# TEMPLATE_Circuit.net
KiCad netlist of a schematic drawn in Altium Designer
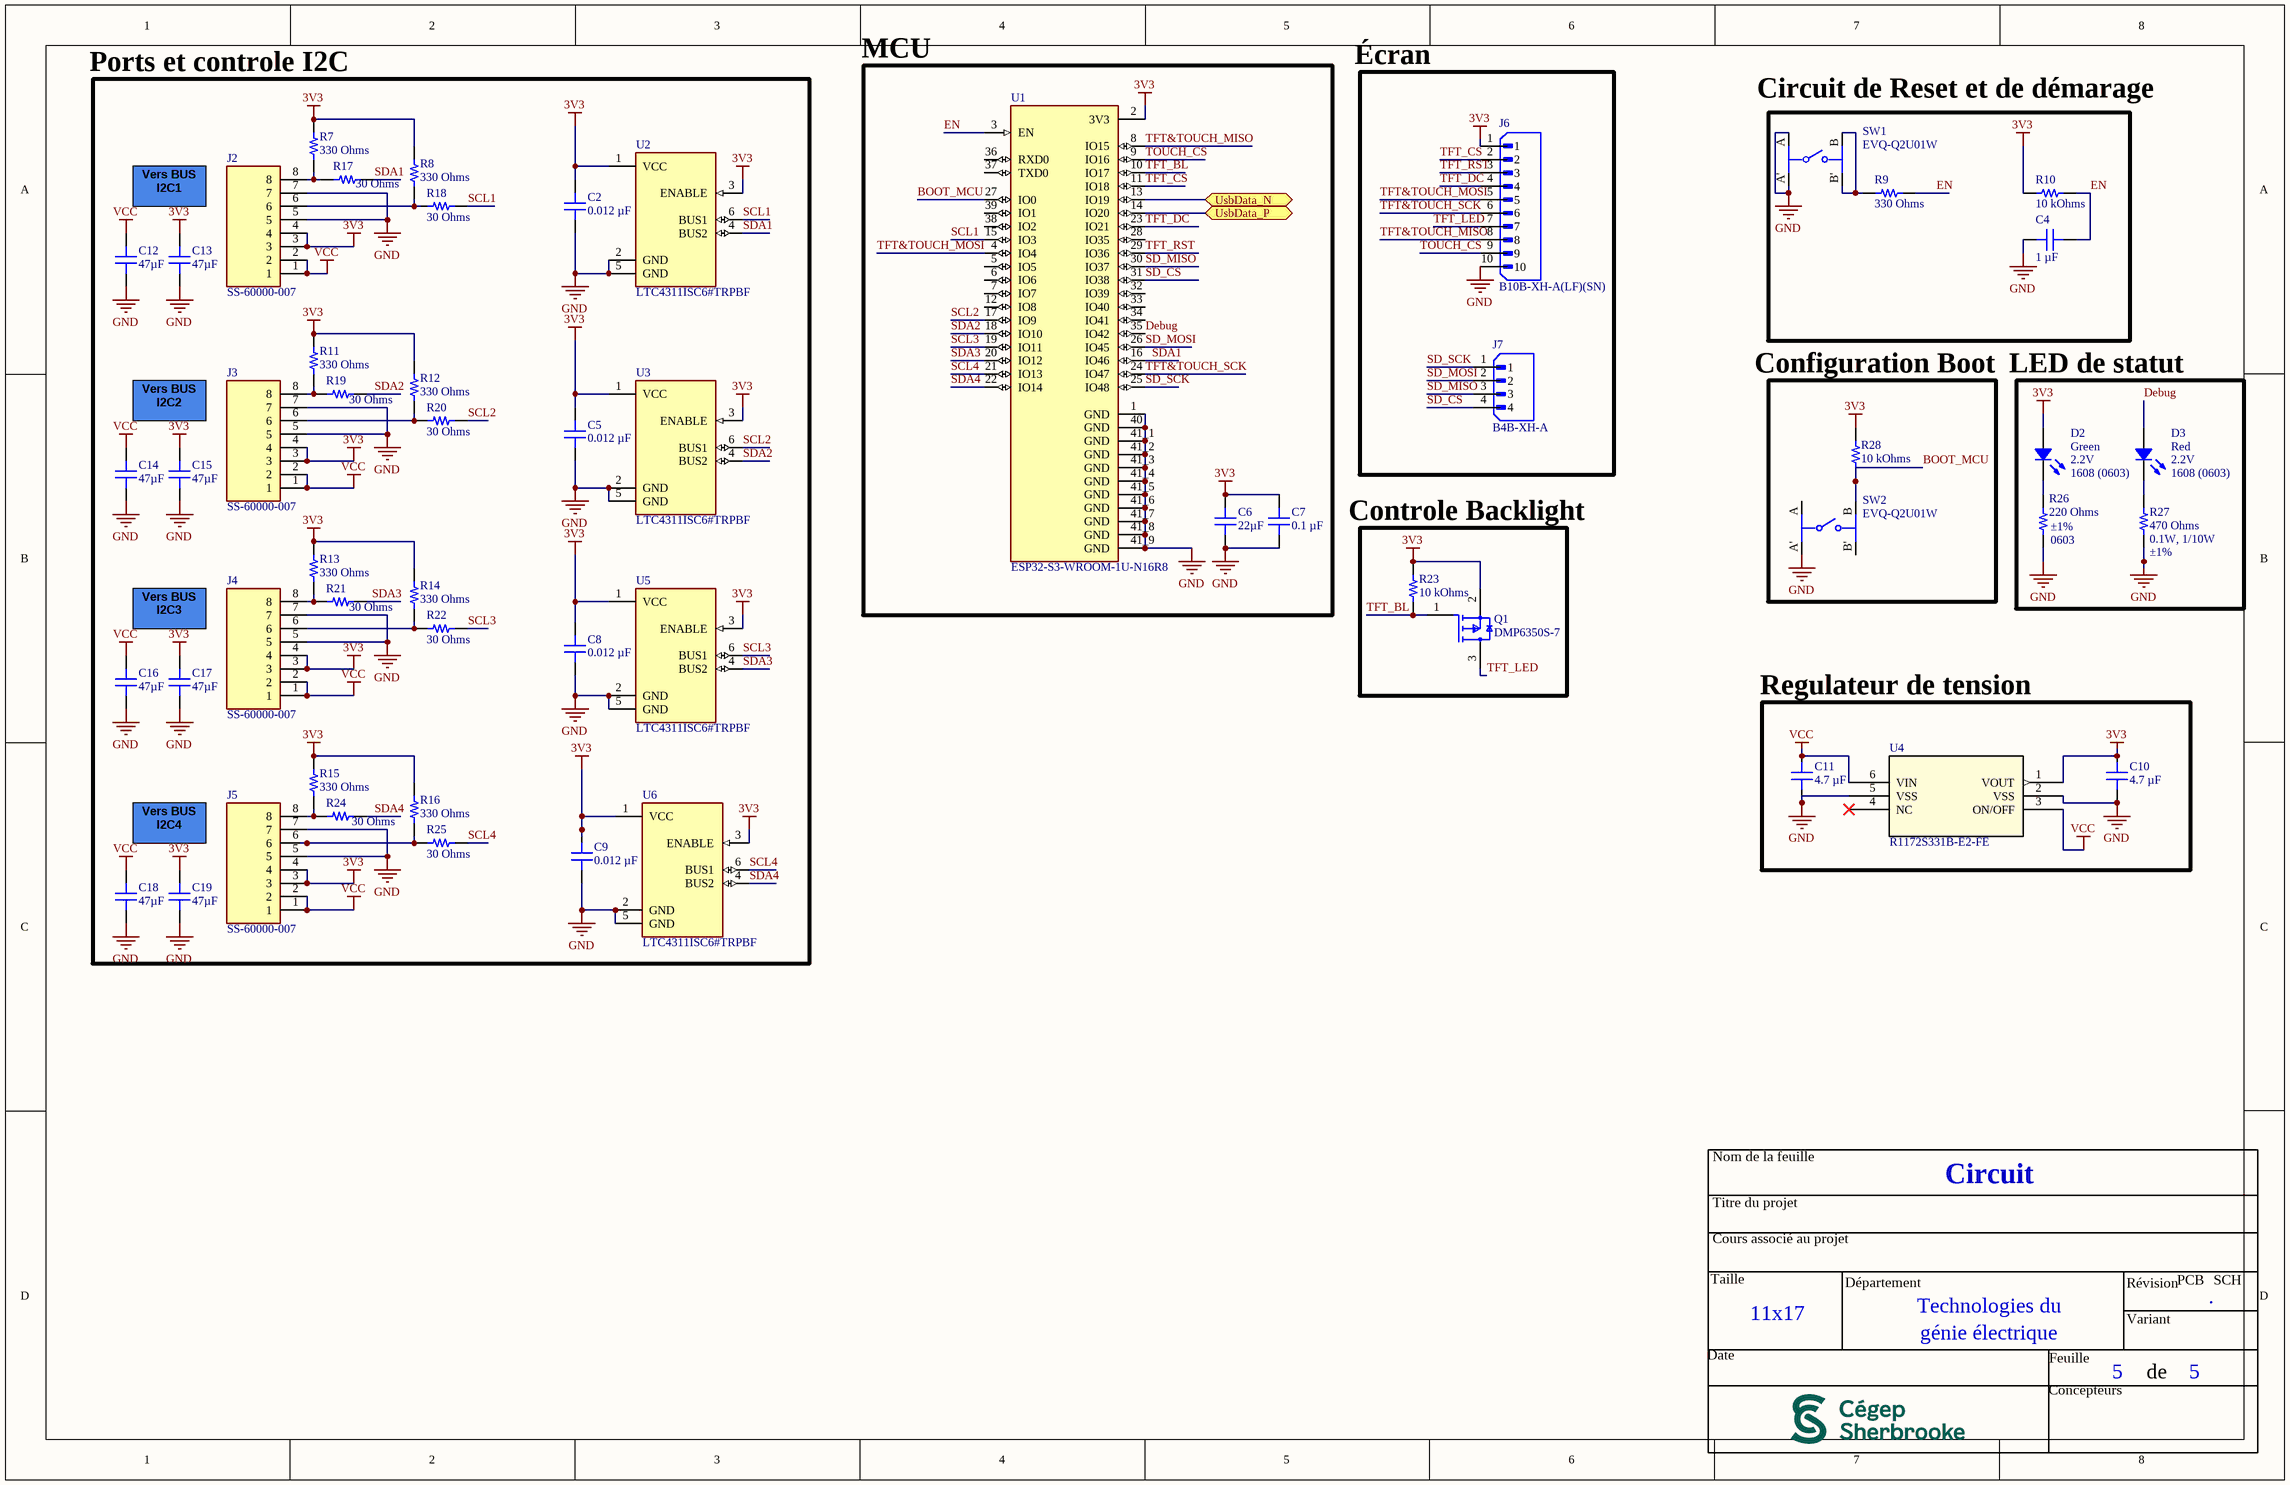
[diagram p0: TEMPLATE_Circuit.SchDoc]

(export (version "E")
  (design (tool "Eeschema 10.0.6"))
  (components
    (comp (ref "C2")
      (value "0.012 µF")
      (footprint "CAP 0603_1608")
      (description "CAP CER 0.012UF 16V X7R 0603")
      (fields (field (name "PART NUMBER") "CC0603KRX7R7BB123") (field (name "MANUFACTURER") "Yageo"))
      (libsource (lib "Celestial Altium Library - altium_library") (part "Capacitor"))
    )
    (comp (ref "C4")
      (value "1 µF")
      (footprint "CAP 0603_1608")
      (description "CAP CER 1UF 16V X7R 0603")
      (fields (field (name "PART NUMBER") "C0603X105M4RACAUTO") (field (name "MANUFACTURER") "KEMET"))
      (libsource (lib "Celestial Altium Library - altium_library") (part "Capacitor"))
    )
    (comp (ref "C5")
      (value "0.012 µF")
      (footprint "CAP 0603_1608")
      (description "CAP CER 0.012UF 16V X7R 0603")
      (fields (field (name "PART NUMBER") "CC0603KRX7R7BB123") (field (name "MANUFACTURER") "Yageo"))
      (libsource (lib "Celestial Altium Library - altium_library") (part "Capacitor"))
    )
    (comp (ref "C6")
      (value "22µF")
      (footprint "CAP 0603_1608")
      (description "CAP CER 22UF 6.3V X5R 0603")
      (fields (field (name "PART NUMBER") "06036D226MAT2A") (field (name "MANUFACTURER") "AVX Corporation"))
      (libsource (lib "Celestial Altium Library - altium_library") (part "Capacitor"))
    )
    (comp (ref "C7")
      (value "0.1 µF")
      (footprint "CAP 0603_1608")
      (description "CAP CER 0.1UF 16V X7R 0603")
      (fields (field (name "PART NUMBER") "C0603C104M4RAC7411") (field (name "MANUFACTURER") "KEMET"))
      (libsource (lib "Celestial Altium Library - altium_library") (part "Capacitor"))
    )
    (comp (ref "C8")
      (value "0.012 µF")
      (footprint "CAP 0603_1608")
      (description "CAP CER 0.012UF 16V X7R 0603")
      (fields (field (name "PART NUMBER") "CC0603KRX7R7BB123") (field (name "MANUFACTURER") "Yageo"))
      (libsource (lib "Celestial Altium Library - altium_library") (part "Capacitor"))
    )
    (comp (ref "C9")
      (value "0.012 µF")
      (footprint "CAP 0603_1608")
      (description "CAP CER 0.012UF 16V X7R 0603")
      (fields (field (name "PART NUMBER") "CC0603KRX7R7BB123") (field (name "MANUFACTURER") "Yageo"))
      (libsource (lib "Celestial Altium Library - altium_library") (part "Capacitor"))
    )
    (comp (ref "C10")
      (value "4.7 µF")
      (footprint "MURATA GRM188 0603_1608")
      (description "CAP CER 4.7UF 16V X6S 0603")
      (fields
        (field (name "PART NUMBER") "GRM188C81C475KE11D")
        (field (name "MANUFACTURER") "Murata Electronics")
      )
      (libsource (lib "Celestial Altium Library - altium_library") (part "Capacitor"))
    )
    (comp (ref "C11")
      (value "4.7 µF")
      (footprint "MURATA GRM188 0603_1608")
      (description "CAP CER 4.7UF 16V X6S 0603")
      (fields
        (field (name "PART NUMBER") "GRM188C81C475KE11D")
        (field (name "MANUFACTURER") "Murata Electronics")
      )
      (libsource (lib "Celestial Altium Library - altium_library") (part "Capacitor"))
    )
    (comp (ref "C12")
      (value "47µF")
      (footprint "CAP 0603_1608")
      (description "CAP CER 47UF 6.3V X5R 0603")
      (fields (field (name "PART NUMBER") "06036D476MAT2A") (field (name "MANUFACTURER") "AVX Corporation"))
      (libsource (lib "Celestial Altium Library - altium_library") (part "Capacitor"))
    )
    (comp (ref "C13")
      (value "47µF")
      (footprint "CAP 0603_1608")
      (description "CAP CER 47UF 6.3V X5R 0603")
      (fields (field (name "PART NUMBER") "06036D476MAT2A") (field (name "MANUFACTURER") "AVX Corporation"))
      (libsource (lib "Celestial Altium Library - altium_library") (part "Capacitor"))
    )
    (comp (ref "C14")
      (value "47µF")
      (footprint "CAP 0603_1608")
      (description "CAP CER 47UF 6.3V X5R 0603")
      (fields (field (name "PART NUMBER") "06036D476MAT2A") (field (name "MANUFACTURER") "AVX Corporation"))
      (libsource (lib "Celestial Altium Library - altium_library") (part "Capacitor"))
    )
    (comp (ref "C15")
      (value "47µF")
      (footprint "CAP 0603_1608")
      (description "CAP CER 47UF 6.3V X5R 0603")
      (fields (field (name "PART NUMBER") "06036D476MAT2A") (field (name "MANUFACTURER") "AVX Corporation"))
      (libsource (lib "Celestial Altium Library - altium_library") (part "Capacitor"))
    )
    (comp (ref "C16")
      (value "47µF")
      (footprint "CAP 0603_1608")
      (description "CAP CER 47UF 6.3V X5R 0603")
      (fields (field (name "PART NUMBER") "06036D476MAT2A") (field (name "MANUFACTURER") "AVX Corporation"))
      (libsource (lib "Celestial Altium Library - altium_library") (part "Capacitor"))
    )
    (comp (ref "C17")
      (value "47µF")
      (footprint "CAP 0603_1608")
      (description "CAP CER 47UF 6.3V X5R 0603")
      (fields (field (name "PART NUMBER") "06036D476MAT2A") (field (name "MANUFACTURER") "AVX Corporation"))
      (libsource (lib "Celestial Altium Library - altium_library") (part "Capacitor"))
    )
    (comp (ref "C18")
      (value "47µF")
      (footprint "CAP 0603_1608")
      (description "CAP CER 47UF 6.3V X5R 0603")
      (fields (field (name "PART NUMBER") "06036D476MAT2A") (field (name "MANUFACTURER") "AVX Corporation"))
      (libsource (lib "Celestial Altium Library - altium_library") (part "Capacitor"))
    )
    (comp (ref "C19")
      (value "47µF")
      (footprint "CAP 0603_1608")
      (description "CAP CER 47UF 6.3V X5R 0603")
      (fields (field (name "PART NUMBER") "06036D476MAT2A") (field (name "MANUFACTURER") "AVX Corporation"))
      (libsource (lib "Celestial Altium Library - altium_library") (part "Capacitor"))
    )
    (comp (ref "D2")
      (value "Green")
      (footprint "LED 0603_1608 GREEN")
      (description "LED GREEN DIFFUSED 0603 SMD")
      (fields
        (field (name "PART NUMBER") "SML-D12P8WT86")
        (field (name "MANUFACTURER") "Rohm Semiconductor")
        (field (name "SUPPLIER DEVICE PACKAGE") "1608 (0603)")
        (field (name "VOLTAGE - FORWARD (VF) (TYP)") "2.2V")
      )
      (libsource (lib "Celestial Altium Library - altium_library") (part "LED"))
    )
    (comp (ref "D3")
      (value "Red")
      (footprint "LED 0603_1608 RED")
      (description "LED RED DIFFUSED 1608 SMD")
      (fields
        (field (name "PART NUMBER") "SML-D12U1WT86")
        (field (name "MANUFACTURER") "Rohm Semiconductor")
        (field (name "SUPPLIER DEVICE PACKAGE") "1608 (0603)")
        (field (name "VOLTAGE - FORWARD (VF) (TYP)") "2.2V")
      )
      (libsource (lib "Celestial Altium Library - altium_library") (part "LED"))
    )
    (comp (ref "J2")
      (value "SS-60000-007")
      (footprint "BEL_SS-60000-007")
      (description "Jack Modular Connector 8p8c _RJ45, Ethernet_ Vertical Unshielded Cat6")
      (fields (field (name "DIGI-KEY_PART_NUMBER") "380-1094-5-ND") (field (name "MF") "Stewart Connector"))
      (libsource (lib "SS-60000-007") (part "SS-60000-007"))
    )
    (comp (ref "J3")
      (value "SS-60000-007")
      (footprint "BEL_SS-60000-007")
      (description "Jack Modular Connector 8p8c _RJ45, Ethernet_ Vertical Unshielded Cat6")
      (fields (field (name "DIGI-KEY_PART_NUMBER") "380-1094-5-ND") (field (name "MF") "Stewart Connector"))
      (libsource (lib "SS-60000-007") (part "SS-60000-007"))
    )
    (comp (ref "J4")
      (value "SS-60000-007")
      (footprint "BEL_SS-60000-007")
      (description "Jack Modular Connector 8p8c _RJ45, Ethernet_ Vertical Unshielded Cat6")
      (fields (field (name "DIGI-KEY_PART_NUMBER") "380-1094-5-ND") (field (name "MF") "Stewart Connector"))
      (libsource (lib "SS-60000-007") (part "SS-60000-007"))
    )
    (comp (ref "J5")
      (value "SS-60000-007")
      (footprint "BEL_SS-60000-007")
      (description "Jack Modular Connector 8p8c _RJ45, Ethernet_ Vertical Unshielded Cat6")
      (fields (field (name "DIGI-KEY_PART_NUMBER") "380-1094-5-ND") (field (name "MF") "Stewart Connector"))
      (libsource (lib "SS-60000-007") (part "SS-60000-007"))
    )
    (comp (ref "J6")
      (value "B10B-XH-A(LF)(SN)")
      (footprint "JST_B10B-XH-A(LF)(SN)")
      (description "Connector Header Through Hole 10 position 0.098 (2.50mm)")
      (fields (field (name "MF") "JST Sales"))
      (libsource (lib "B10B-XH-A_LF__SN_") (part "B10B-XH-A(LF)(SN)"))
    )
    (comp (ref "J7")
      (value "B4B-XH-A")
      (footprint "JST_B4B-XH-A")
      (fields (field (name "MF") "{'manufacturer': u'JST Sales America Inc.'}"))
      (libsource (lib "B4B-XH-A") (part "B4B-XH-A"))
    )
    (comp (ref "Q1")
      (value "DMP6350S-7")
      (footprint "FP-SOT23-MFG")
      (description "MOSFET P-CHA 60V 720MW SOT23")
      (libsource (lib "Altium Content Vault") (part "3dbb74db695b7d0c4d5bfcbdbe83ddf"))
    )
    (comp (ref "R7")
      (value "330 Ohms")
      (footprint "RES 0603_1608")
      (description "RES SMD 330 OHM 1% 1/5W 0603")
      (fields
        (field (name "PART NUMBER") "CRGH0603F330R")
        (field (name "MANUFACTURER") "TE Connectivity Passive Product")
      )
      (libsource (lib "Celestial Altium Library - altium_library") (part "Resistor"))
    )
    (comp (ref "R8")
      (value "330 Ohms")
      (footprint "RES 0603_1608")
      (description "RES SMD 330 OHM 1% 1/5W 0603")
      (fields
        (field (name "PART NUMBER") "CRGH0603F330R")
        (field (name "MANUFACTURER") "TE Connectivity Passive Product")
      )
      (libsource (lib "Celestial Altium Library - altium_library") (part "Resistor"))
    )
    (comp (ref "R9")
      (value "330 Ohms")
      (footprint "RES 0603_1608")
      (description "RES SMD 330 OHM 1% 1/5W 0603")
      (fields
        (field (name "PART NUMBER") "CRGH0603F330R")
        (field (name "MANUFACTURER") "TE Connectivity Passive Product")
      )
      (libsource (lib "Celestial Altium Library - altium_library") (part "Resistor"))
    )
    (comp (ref "R10")
      (value "10 kOhms")
      (footprint "RES 0603_1608")
      (description "RES SMD 10K OHM 5% 1/4W 0603")
      (fields (field (name "PART NUMBER") "RCS060310K0JNEA") (field (name "MANUFACTURER") "Vishay Dale"))
      (libsource (lib "Celestial Altium Library - altium_library") (part "Resistor"))
    )
    (comp (ref "R11")
      (value "330 Ohms")
      (footprint "RES 0603_1608")
      (description "RES SMD 330 OHM 1% 1/5W 0603")
      (fields
        (field (name "PART NUMBER") "CRGH0603F330R")
        (field (name "MANUFACTURER") "TE Connectivity Passive Product")
      )
      (libsource (lib "Celestial Altium Library - altium_library") (part "Resistor"))
    )
    (comp (ref "R12")
      (value "330 Ohms")
      (footprint "RES 0603_1608")
      (description "RES SMD 330 OHM 1% 1/5W 0603")
      (fields
        (field (name "PART NUMBER") "CRGH0603F330R")
        (field (name "MANUFACTURER") "TE Connectivity Passive Product")
      )
      (libsource (lib "Celestial Altium Library - altium_library") (part "Resistor"))
    )
    (comp (ref "R13")
      (value "330 Ohms")
      (footprint "RES 0603_1608")
      (description "RES SMD 330 OHM 1% 1/5W 0603")
      (fields
        (field (name "PART NUMBER") "CRGH0603F330R")
        (field (name "MANUFACTURER") "TE Connectivity Passive Product")
      )
      (libsource (lib "Celestial Altium Library - altium_library") (part "Resistor"))
    )
    (comp (ref "R14")
      (value "330 Ohms")
      (footprint "RES 0603_1608")
      (description "RES SMD 330 OHM 1% 1/5W 0603")
      (fields
        (field (name "PART NUMBER") "CRGH0603F330R")
        (field (name "MANUFACTURER") "TE Connectivity Passive Product")
      )
      (libsource (lib "Celestial Altium Library - altium_library") (part "Resistor"))
    )
    (comp (ref "R15")
      (value "330 Ohms")
      (footprint "RES 0603_1608")
      (description "RES SMD 330 OHM 1% 1/5W 0603")
      (fields
        (field (name "PART NUMBER") "CRGH0603F330R")
        (field (name "MANUFACTURER") "TE Connectivity Passive Product")
      )
      (libsource (lib "Celestial Altium Library - altium_library") (part "Resistor"))
    )
    (comp (ref "R16")
      (value "330 Ohms")
      (footprint "RES 0603_1608")
      (description "RES SMD 330 OHM 1% 1/5W 0603")
      (fields
        (field (name "PART NUMBER") "CRGH0603F330R")
        (field (name "MANUFACTURER") "TE Connectivity Passive Product")
      )
      (libsource (lib "Celestial Altium Library - altium_library") (part "Resistor"))
    )
    (comp (ref "R17")
      (value "30 Ohms")
      (footprint "RES 0603_1608")
      (description "RES SMD 30 OHM 5% 1/4W 0603")
      (fields (field (name "PART NUMBER") "ESR03EZPJ300") (field (name "MANUFACTURER") "Rohm Semiconductor"))
      (libsource (lib "Celestial Altium Library - altium_library") (part "Resistor"))
    )
    (comp (ref "R18")
      (value "30 Ohms")
      (footprint "RES 0603_1608")
      (description "RES SMD 30 OHM 5% 1/4W 0603")
      (fields (field (name "PART NUMBER") "ESR03EZPJ300") (field (name "MANUFACTURER") "Rohm Semiconductor"))
      (libsource (lib "Celestial Altium Library - altium_library") (part "Resistor"))
    )
    (comp (ref "R19")
      (value "30 Ohms")
      (footprint "RES 0603_1608")
      (description "RES SMD 30 OHM 5% 1/4W 0603")
      (fields (field (name "PART NUMBER") "ESR03EZPJ300") (field (name "MANUFACTURER") "Rohm Semiconductor"))
      (libsource (lib "Celestial Altium Library - altium_library") (part "Resistor"))
    )
    (comp (ref "R20")
      (value "30 Ohms")
      (footprint "RES 0603_1608")
      (description "RES SMD 30 OHM 5% 1/4W 0603")
      (fields (field (name "PART NUMBER") "ESR03EZPJ300") (field (name "MANUFACTURER") "Rohm Semiconductor"))
      (libsource (lib "Celestial Altium Library - altium_library") (part "Resistor"))
    )
    (comp (ref "R21")
      (value "30 Ohms")
      (footprint "RES 0603_1608")
      (description "RES SMD 30 OHM 5% 1/4W 0603")
      (fields (field (name "PART NUMBER") "ESR03EZPJ300") (field (name "MANUFACTURER") "Rohm Semiconductor"))
      (libsource (lib "Celestial Altium Library - altium_library") (part "Resistor"))
    )
    (comp (ref "R22")
      (value "30 Ohms")
      (footprint "RES 0603_1608")
      (description "RES SMD 30 OHM 5% 1/4W 0603")
      (fields (field (name "PART NUMBER") "ESR03EZPJ300") (field (name "MANUFACTURER") "Rohm Semiconductor"))
      (libsource (lib "Celestial Altium Library - altium_library") (part "Resistor"))
    )
    (comp (ref "R23")
      (value "10 kOhms")
      (footprint "RES 0603_1608")
      (description "RES SMD 10K OHM 5% 1/4W 0603")
      (fields (field (name "PART NUMBER") "RCS060310K0JNEA") (field (name "MANUFACTURER") "Vishay Dale"))
      (libsource (lib "Celestial Altium Library - altium_library") (part "Resistor"))
    )
    (comp (ref "R24")
      (value "30 Ohms")
      (footprint "RES 0603_1608")
      (description "RES SMD 30 OHM 5% 1/4W 0603")
      (fields (field (name "PART NUMBER") "ESR03EZPJ300") (field (name "MANUFACTURER") "Rohm Semiconductor"))
      (libsource (lib "Celestial Altium Library - altium_library") (part "Resistor"))
    )
    (comp (ref "R25")
      (value "30 Ohms")
      (footprint "RES 0603_1608")
      (description "RES SMD 30 OHM 5% 1/4W 0603")
      (fields (field (name "PART NUMBER") "ESR03EZPJ300") (field (name "MANUFACTURER") "Rohm Semiconductor"))
      (libsource (lib "Celestial Altium Library - altium_library") (part "Resistor"))
    )
    (comp (ref "R26")
      (value "220 Ohms")
      (footprint "RES 0603_1608")
      (description "RES SMD 220 OHM 1% 1/10W 0603")
      (fields
        (field (name "PART NUMBER") "CR0603-FX-2200ELF")
        (field (name "MANUFACTURER") "Bourns Inc.")
        (field (name "SUPPLIER DEVICE PACKAGE") "0603")
        (field (name "TOLERANCE") "±1%")
      )
      (libsource (lib "Celestial Altium Library - altium_library") (part "Resistor"))
    )
    (comp (ref "R27")
      (value "470 Ohms")
      (footprint "RES 0603_1608")
      (description "RES SMD 470 OHM 1% 1/10W 0603")
      (fields
        (field (name "PART NUMBER") "ERJ-3EKF4700V")
        (field (name "MANUFACTURER") "Panasonic Electronic Components")
        (field (name "POWER (WATTS)") "0.1W, 1/10W")
        (field (name "TOLERANCE") "±1%")
      )
      (libsource (lib "Celestial Altium Library - altium_library") (part "Resistor"))
    )
    (comp (ref "R28")
      (value "10 kOhms")
      (footprint "RES 0603_1608")
      (description "RES SMD 10K OHM 5% 1/4W 0603")
      (fields (field (name "PART NUMBER") "RCS060310K0JNEA") (field (name "MANUFACTURER") "Vishay Dale"))
      (libsource (lib "Celestial Altium Library - altium_library") (part "Resistor"))
    )
    (comp (ref "SW1")
      (value "EVQ-Q2U01W")
      (footprint "FP-EVQ-Q2U01W-MFG")
      (description "SWITCH TACTILE SPST-NO 0.02A 15V")
      (libsource (lib "Altium Content Vault") (part "9677229990528492022b31d4503349f"))
    )
    (comp (ref "SW2")
      (value "EVQ-Q2U01W")
      (footprint "FP-EVQ-Q2U01W-MFG")
      (description "SWITCH TACTILE SPST-NO 0.02A 15V")
      (libsource (lib "Altium Content Vault") (part "9677229990528492022b31d4503349f"))
    )
    (comp (ref "U1")
      (value "ESP32-S3-WROOM-1U-N16R8")
      (footprint "XCVR_ESP32-S3-WROOM-1U-N16R8")
      (fields (field (name "MF") "Espressif Systems"))
      (libsource (lib "ESP32-S3-WROOM-1U-N16R8") (part "ESP32-S3-WROOM-1U-N16R8"))
    )
    (comp (ref "U2")
      (value "LTC4311ISC6#TRPBF")
      (footprint "SOT65P210X100-6N")
      (description "Low Voltage I2C/SMBus Accelerator")
      (fields (field (name "MF") "Analog Devices"))
      (libsource (lib "LTC4311ISC6_TRPBF") (part "LTC4311ISC6#TRPBF"))
    )
    (comp (ref "U3")
      (value "LTC4311ISC6#TRPBF")
      (footprint "SOT65P210X100-6N")
      (description "Low Voltage I2C/SMBus Accelerator")
      (fields (field (name "MF") "Analog Devices"))
      (libsource (lib "LTC4311ISC6_TRPBF") (part "LTC4311ISC6#TRPBF"))
    )
    (comp (ref "U4")
      (value "R1172S331B-E2-FE")
      (footprint "HSOP-6_FH006-A-P-SD-2.1_ABL")
      (description "No Description Available")
      (libsource (lib "S-1172B33-E6T1U") (part "S-1172B33-E6T1U"))
    )
    (comp (ref "U5")
      (value "LTC4311ISC6#TRPBF")
      (footprint "SOT65P210X100-6N")
      (description "Low Voltage I2C/SMBus Accelerator")
      (fields (field (name "MF") "Analog Devices"))
      (libsource (lib "LTC4311ISC6_TRPBF") (part "LTC4311ISC6#TRPBF"))
    )
    (comp (ref "U6")
      (value "LTC4311ISC6#TRPBF")
      (footprint "SOT65P210X100-6N")
      (description "Low Voltage I2C/SMBus Accelerator")
      (fields (field (name "MF") "Analog Devices"))
      (libsource (lib "LTC4311ISC6_TRPBF") (part "LTC4311ISC6#TRPBF"))
    )
  )
  (nets
    (net (code "1") (name "/BOOT_MCU") (class "Default")
      (node (ref "R28") (pin "2") (pinfunction "2_2") (pintype "passive"))
      (node (ref "SW2") (pin "B") (pinfunction "B_B") (pintype "passive"))
      (node (ref "U1") (pin "27") (pinfunction "IO0_27") (pintype "bidirectional"))
    )
    (net (code "2") (name "/Debug") (class "Default")
      (node (ref "D3") (pin "1") (pinfunction "1_1") (pintype "passive"))
      (node (ref "U1") (pin "35") (pinfunction "IO42_35") (pintype "bidirectional"))
    )
    (net (code "3") (name "/EN") (class "Default")
      (node (ref "C4") (pin "1") (pinfunction "1_1") (pintype "passive"))
      (node (ref "R10") (pin "2") (pinfunction "2_2") (pintype "passive"))
      (node (ref "R9") (pin "1") (pinfunction "1_1") (pintype "passive"))
      (node (ref "U1") (pin "3") (pinfunction "EN_3") (pintype "input"))
    )
    (net (code "4") (name "/SCL1") (class "Default")
      (node (ref "R18") (pin "2") (pinfunction "2_2") (pintype "passive"))
      (node (ref "U1") (pin "15") (pinfunction "IO3_15") (pintype "bidirectional"))
      (node (ref "U2") (pin "6") (pinfunction "BUS1_6") (pintype "bidirectional"))
    )
    (net (code "5") (name "/SCL2") (class "Default")
      (node (ref "R20") (pin "2") (pinfunction "2_2") (pintype "passive"))
      (node (ref "U1") (pin "17") (pinfunction "IO9_17") (pintype "bidirectional"))
      (node (ref "U3") (pin "6") (pinfunction "BUS1_6") (pintype "bidirectional"))
    )
    (net (code "6") (name "/SCL3") (class "Default")
      (node (ref "R22") (pin "2") (pinfunction "2_2") (pintype "passive"))
      (node (ref "U1") (pin "19") (pinfunction "IO11_19") (pintype "bidirectional"))
      (node (ref "U5") (pin "6") (pinfunction "BUS1_6") (pintype "bidirectional"))
    )
    (net (code "7") (name "/SCL4") (class "Default")
      (node (ref "R25") (pin "2") (pinfunction "2_2") (pintype "passive"))
      (node (ref "U1") (pin "21") (pinfunction "IO13_21") (pintype "bidirectional"))
      (node (ref "U6") (pin "6") (pinfunction "BUS1_6") (pintype "bidirectional"))
    )
    (net (code "8") (name "/SDA1") (class "Default")
      (node (ref "R17") (pin "2") (pinfunction "2_2") (pintype "passive"))
      (node (ref "U1") (pin "16") (pinfunction "IO46_16") (pintype "bidirectional"))
      (node (ref "U2") (pin "4") (pinfunction "BUS2_4") (pintype "bidirectional"))
    )
    (net (code "9") (name "/SDA2") (class "Default")
      (node (ref "R19") (pin "2") (pinfunction "2_2") (pintype "passive"))
      (node (ref "U1") (pin "18") (pinfunction "IO10_18") (pintype "bidirectional"))
      (node (ref "U3") (pin "4") (pinfunction "BUS2_4") (pintype "bidirectional"))
    )
    (net (code "10") (name "/SDA3") (class "Default")
      (node (ref "R21") (pin "2") (pinfunction "2_2") (pintype "passive"))
      (node (ref "U1") (pin "20") (pinfunction "IO12_20") (pintype "bidirectional"))
      (node (ref "U5") (pin "4") (pinfunction "BUS2_4") (pintype "bidirectional"))
    )
    (net (code "11") (name "/SDA4") (class "Default")
      (node (ref "R24") (pin "2") (pinfunction "2_2") (pintype "passive"))
      (node (ref "U1") (pin "22") (pinfunction "IO14_22") (pintype "bidirectional"))
      (node (ref "U6") (pin "4") (pinfunction "BUS2_4") (pintype "bidirectional"))
    )
    (net (code "12") (name "/SD_CS") (class "Default")
      (node (ref "J7") (pin "4") (pinfunction "4_4") (pintype "passive"))
      (node (ref "U1") (pin "31") (pinfunction "IO38_31") (pintype "bidirectional"))
    )
    (net (code "13") (name "/SD_MISO") (class "Default")
      (node (ref "J7") (pin "3") (pinfunction "3_3") (pintype "passive"))
      (node (ref "U1") (pin "30") (pinfunction "IO37_30") (pintype "bidirectional"))
    )
    (net (code "14") (name "/SD_MOSI") (class "Default")
      (node (ref "J7") (pin "2") (pinfunction "2_2") (pintype "passive"))
      (node (ref "U1") (pin "26") (pinfunction "IO45_26") (pintype "bidirectional"))
    )
    (net (code "15") (name "/SD_SCK") (class "Default")
      (node (ref "J7") (pin "1") (pinfunction "1_1") (pintype "passive"))
      (node (ref "U1") (pin "25") (pinfunction "IO48_25") (pintype "bidirectional"))
    )
    (net (code "16") (name "/TFT&TOUCH_MISO") (class "Default")
      (node (ref "J6") (pin "8") (pinfunction "8_8") (pintype "passive"))
      (node (ref "U1") (pin "8") (pinfunction "IO15_8") (pintype "bidirectional"))
    )
    (net (code "17") (name "/TFT&TOUCH_MOSI") (class "Default")
      (node (ref "J6") (pin "5") (pinfunction "5_5") (pintype "passive"))
      (node (ref "U1") (pin "4") (pinfunction "IO4_4") (pintype "bidirectional"))
    )
    (net (code "18") (name "/TFT&TOUCH_SCK") (class "Default")
      (node (ref "J6") (pin "6") (pinfunction "6_6") (pintype "passive"))
      (node (ref "U1") (pin "24") (pinfunction "IO47_24") (pintype "bidirectional"))
    )
    (net (code "19") (name "/TFT_BL") (class "Default")
      (node (ref "Q1") (pin "1") (pinfunction "G_1") (pintype "passive"))
      (node (ref "R23") (pin "1") (pinfunction "1_1") (pintype "passive"))
      (node (ref "U1") (pin "10") (pinfunction "IO17_10") (pintype "bidirectional"))
    )
    (net (code "20") (name "/TFT_CS") (class "Default")
      (node (ref "J6") (pin "2") (pinfunction "2_2") (pintype "passive"))
      (node (ref "U1") (pin "11") (pinfunction "IO18_11") (pintype "bidirectional"))
    )
    (net (code "21") (name "/TFT_DC") (class "Default")
      (node (ref "J6") (pin "4") (pinfunction "4_4") (pintype "passive"))
      (node (ref "U1") (pin "23") (pinfunction "IO21_23") (pintype "bidirectional"))
    )
    (net (code "22") (name "/TFT_LED") (class "Default")
      (node (ref "J6") (pin "7") (pinfunction "7_7") (pintype "passive"))
      (node (ref "Q1") (pin "3") (pinfunction "D_3") (pintype "passive"))
    )
    (net (code "23") (name "/TFT_RST") (class "Default")
      (node (ref "J6") (pin "3") (pinfunction "3_3") (pintype "passive"))
      (node (ref "U1") (pin "29") (pinfunction "IO36_29") (pintype "bidirectional"))
    )
    (net (code "24") (name "/TOUCH_CS") (class "Default")
      (node (ref "J6") (pin "9") (pinfunction "9_9") (pintype "passive"))
      (node (ref "U1") (pin "9") (pinfunction "IO16_9") (pintype "bidirectional"))
    )
    (net (code "25") (name "/UsbData_N") (class "Default")
      (node (ref "U1") (pin "13") (pinfunction "IO19_13") (pintype "bidirectional"))
    )
    (net (code "26") (name "/UsbData_P") (class "Default")
      (node (ref "U1") (pin "14") (pinfunction "IO20_14") (pintype "bidirectional"))
    )
    (net (code "27") (name "3V3") (class "Default")
      (node (ref "C10") (pin "1") (pinfunction "1_1") (pintype "passive"))
      (node (ref "C13") (pin "2") (pinfunction "2_2") (pintype "passive"))
      (node (ref "C15") (pin "2") (pinfunction "2_2") (pintype "passive"))
      (node (ref "C17") (pin "2") (pinfunction "2_2") (pintype "passive"))
      (node (ref "C19") (pin "2") (pinfunction "2_2") (pintype "passive"))
      (node (ref "C2") (pin "2") (pinfunction "2_2") (pintype "passive"))
      (node (ref "C5") (pin "2") (pinfunction "2_2") (pintype "passive"))
      (node (ref "C6") (pin "2") (pinfunction "2_2") (pintype "passive"))
      (node (ref "C7") (pin "2") (pinfunction "2_2") (pintype "passive"))
      (node (ref "C8") (pin "2") (pinfunction "2_2") (pintype "passive"))
      (node (ref "C9") (pin "2") (pinfunction "2_2") (pintype "passive"))
      (node (ref "D2") (pin "1") (pinfunction "1_1") (pintype "passive"))
      (node (ref "J2") (pin "3") (pinfunction "3_3") (pintype "passive"))
      (node (ref "J2") (pin "4") (pinfunction "4_4") (pintype "passive"))
      (node (ref "J3") (pin "3") (pinfunction "3_3") (pintype "passive"))
      (node (ref "J3") (pin "4") (pinfunction "4_4") (pintype "passive"))
      (node (ref "J4") (pin "3") (pinfunction "3_3") (pintype "passive"))
      (node (ref "J4") (pin "4") (pinfunction "4_4") (pintype "passive"))
      (node (ref "J5") (pin "3") (pinfunction "3_3") (pintype "passive"))
      (node (ref "J5") (pin "4") (pinfunction "4_4") (pintype "passive"))
      (node (ref "J6") (pin "1") (pinfunction "1_1") (pintype "passive"))
      (node (ref "Q1") (pin "2") (pinfunction "S_2") (pintype "passive"))
      (node (ref "R10") (pin "1") (pinfunction "1_1") (pintype "passive"))
      (node (ref "R11") (pin "2") (pinfunction "2_2") (pintype "passive"))
      (node (ref "R12") (pin "2") (pinfunction "2_2") (pintype "passive"))
      (node (ref "R13") (pin "2") (pinfunction "2_2") (pintype "passive"))
      (node (ref "R14") (pin "2") (pinfunction "2_2") (pintype "passive"))
      (node (ref "R15") (pin "2") (pinfunction "2_2") (pintype "passive"))
      (node (ref "R16") (pin "2") (pinfunction "2_2") (pintype "passive"))
      (node (ref "R23") (pin "2") (pinfunction "2_2") (pintype "passive"))
      (node (ref "R28") (pin "1") (pinfunction "1_1") (pintype "passive"))
      (node (ref "R7") (pin "2") (pinfunction "2_2") (pintype "passive"))
      (node (ref "R8") (pin "2") (pinfunction "2_2") (pintype "passive"))
      (node (ref "U1") (pin "2") (pinfunction "3V3_2") (pintype "power_in"))
      (node (ref "U2") (pin "1") (pinfunction "VCC_1") (pintype "power_in"))
      (node (ref "U2") (pin "3") (pinfunction "ENABLE_3") (pintype "input"))
      (node (ref "U3") (pin "1") (pinfunction "VCC_1") (pintype "power_in"))
      (node (ref "U3") (pin "3") (pinfunction "ENABLE_3") (pintype "input"))
      (node (ref "U4") (pin "1") (pinfunction "VOUT_1") (pintype "output"))
      (node (ref "U5") (pin "1") (pinfunction "VCC_1") (pintype "power_in"))
      (node (ref "U5") (pin "3") (pinfunction "ENABLE_3") (pintype "input"))
      (node (ref "U6") (pin "1") (pinfunction "VCC_1") (pintype "power_in"))
      (node (ref "U6") (pin "3") (pinfunction "ENABLE_3") (pintype "input"))
    )
    (net (code "28") (name "GND") (class "Default")
      (node (ref "C10") (pin "2") (pinfunction "2_2") (pintype "passive"))
      (node (ref "C11") (pin "1") (pinfunction "1_1") (pintype "passive"))
      (node (ref "C12") (pin "1") (pinfunction "1_1") (pintype "passive"))
      (node (ref "C13") (pin "1") (pinfunction "1_1") (pintype "passive"))
      (node (ref "C14") (pin "1") (pinfunction "1_1") (pintype "passive"))
      (node (ref "C15") (pin "1") (pinfunction "1_1") (pintype "passive"))
      (node (ref "C16") (pin "1") (pinfunction "1_1") (pintype "passive"))
      (node (ref "C17") (pin "1") (pinfunction "1_1") (pintype "passive"))
      (node (ref "C18") (pin "1") (pinfunction "1_1") (pintype "passive"))
      (node (ref "C19") (pin "1") (pinfunction "1_1") (pintype "passive"))
      (node (ref "C2") (pin "1") (pinfunction "1_1") (pintype "passive"))
      (node (ref "C4") (pin "2") (pinfunction "2_2") (pintype "passive"))
      (node (ref "C5") (pin "1") (pinfunction "1_1") (pintype "passive"))
      (node (ref "C6") (pin "1") (pinfunction "1_1") (pintype "passive"))
      (node (ref "C7") (pin "1") (pinfunction "1_1") (pintype "passive"))
      (node (ref "C8") (pin "1") (pinfunction "1_1") (pintype "passive"))
      (node (ref "C9") (pin "1") (pinfunction "1_1") (pintype "passive"))
      (node (ref "J2") (pin "5") (pinfunction "5_5") (pintype "passive"))
      (node (ref "J2") (pin "7") (pinfunction "7_7") (pintype "passive"))
      (node (ref "J3") (pin "5") (pinfunction "5_5") (pintype "passive"))
      (node (ref "J3") (pin "7") (pinfunction "7_7") (pintype "passive"))
      (node (ref "J4") (pin "5") (pinfunction "5_5") (pintype "passive"))
      (node (ref "J4") (pin "7") (pinfunction "7_7") (pintype "passive"))
      (node (ref "J5") (pin "5") (pinfunction "5_5") (pintype "passive"))
      (node (ref "J5") (pin "7") (pinfunction "7_7") (pintype "passive"))
      (node (ref "J6") (pin "10") (pinfunction "10_10") (pintype "passive"))
      (node (ref "R26") (pin "1") (pinfunction "1_1") (pintype "passive"))
      (node (ref "R27") (pin "1") (pinfunction "1_1") (pintype "passive"))
      (node (ref "SW1") (pin "A") (pinfunction "A_A") (pintype "passive"))
      (node (ref "SW1") (pin "A'") (pinfunction "A'_A'") (pintype "passive"))
      (node (ref "SW2") (pin "A'") (pinfunction "A'_A'") (pintype "passive"))
      (node (ref "U1") (pin "1") (pinfunction "GND_1") (pintype "power_in"))
      (node (ref "U1") (pin "40") (pinfunction "GND_40") (pintype "power_in"))
      (node (ref "U1") (pin "41_1") (pinfunction "GND_41_1") (pintype "power_in"))
      (node (ref "U1") (pin "41_2") (pinfunction "GND_41_2") (pintype "power_in"))
      (node (ref "U1") (pin "41_3") (pinfunction "GND_41_3") (pintype "power_in"))
      (node (ref "U1") (pin "41_4") (pinfunction "GND_41_4") (pintype "power_in"))
      (node (ref "U1") (pin "41_5") (pinfunction "GND_41_5") (pintype "power_in"))
      (node (ref "U1") (pin "41_6") (pinfunction "GND_41_6") (pintype "power_in"))
      (node (ref "U1") (pin "41_7") (pinfunction "GND_41_7") (pintype "power_in"))
      (node (ref "U1") (pin "41_8") (pinfunction "GND_41_8") (pintype "power_in"))
      (node (ref "U1") (pin "41_9") (pinfunction "GND_41_9") (pintype "power_in"))
      (node (ref "U2") (pin "2") (pinfunction "GND_2") (pintype "power_in"))
      (node (ref "U2") (pin "5") (pinfunction "GND_5") (pintype "power_in"))
      (node (ref "U3") (pin "2") (pinfunction "GND_2") (pintype "power_in"))
      (node (ref "U3") (pin "5") (pinfunction "GND_5") (pintype "power_in"))
      (node (ref "U4") (pin "2") (pinfunction "VSS_2") (pintype "power_in"))
      (node (ref "U4") (pin "5") (pinfunction "VSS_5") (pintype "power_in"))
      (node (ref "U5") (pin "2") (pinfunction "GND_2") (pintype "power_in"))
      (node (ref "U5") (pin "5") (pinfunction "GND_5") (pintype "power_in"))
      (node (ref "U6") (pin "2") (pinfunction "GND_2") (pintype "power_in"))
      (node (ref "U6") (pin "5") (pinfunction "GND_5") (pintype "power_in"))
    )
    (net (code "29") (name "Net-(D2-Pad2)") (class "Default")
      (node (ref "D2") (pin "2") (pinfunction "2_2") (pintype "passive"))
      (node (ref "R26") (pin "2") (pinfunction "2_2") (pintype "passive"))
    )
    (net (code "30") (name "Net-(D3-Pad2)") (class "Default")
      (node (ref "D3") (pin "2") (pinfunction "2_2") (pintype "passive"))
      (node (ref "R27") (pin "2") (pinfunction "2_2") (pintype "passive"))
    )
    (net (code "31") (name "Net-(J2-Pad6)") (class "Default")
      (node (ref "J2") (pin "6") (pinfunction "6_6") (pintype "passive"))
      (node (ref "R18") (pin "1") (pinfunction "1_1") (pintype "passive"))
      (node (ref "R8") (pin "1") (pinfunction "1_1") (pintype "passive"))
    )
    (net (code "32") (name "Net-(J2-Pad8)") (class "Default")
      (node (ref "J2") (pin "8") (pinfunction "8_8") (pintype "passive"))
      (node (ref "R17") (pin "1") (pinfunction "1_1") (pintype "passive"))
      (node (ref "R7") (pin "1") (pinfunction "1_1") (pintype "passive"))
    )
    (net (code "33") (name "Net-(J3-Pad6)") (class "Default")
      (node (ref "J3") (pin "6") (pinfunction "6_6") (pintype "passive"))
      (node (ref "R12") (pin "1") (pinfunction "1_1") (pintype "passive"))
      (node (ref "R20") (pin "1") (pinfunction "1_1") (pintype "passive"))
    )
    (net (code "34") (name "Net-(J3-Pad8)") (class "Default")
      (node (ref "J3") (pin "8") (pinfunction "8_8") (pintype "passive"))
      (node (ref "R11") (pin "1") (pinfunction "1_1") (pintype "passive"))
      (node (ref "R19") (pin "1") (pinfunction "1_1") (pintype "passive"))
    )
    (net (code "35") (name "Net-(J4-Pad6)") (class "Default")
      (node (ref "J4") (pin "6") (pinfunction "6_6") (pintype "passive"))
      (node (ref "R14") (pin "1") (pinfunction "1_1") (pintype "passive"))
      (node (ref "R22") (pin "1") (pinfunction "1_1") (pintype "passive"))
    )
    (net (code "36") (name "Net-(J4-Pad8)") (class "Default")
      (node (ref "J4") (pin "8") (pinfunction "8_8") (pintype "passive"))
      (node (ref "R13") (pin "1") (pinfunction "1_1") (pintype "passive"))
      (node (ref "R21") (pin "1") (pinfunction "1_1") (pintype "passive"))
    )
    (net (code "37") (name "Net-(J5-Pad6)") (class "Default")
      (node (ref "J5") (pin "6") (pinfunction "6_6") (pintype "passive"))
      (node (ref "R16") (pin "1") (pinfunction "1_1") (pintype "passive"))
      (node (ref "R25") (pin "1") (pinfunction "1_1") (pintype "passive"))
    )
    (net (code "38") (name "Net-(J5-Pad8)") (class "Default")
      (node (ref "J5") (pin "8") (pinfunction "8_8") (pintype "passive"))
      (node (ref "R15") (pin "1") (pinfunction "1_1") (pintype "passive"))
      (node (ref "R24") (pin "1") (pinfunction "1_1") (pintype "passive"))
    )
    (net (code "39") (name "Net-(R9-Pad2)") (class "Default")
      (node (ref "R9") (pin "2") (pinfunction "2_2") (pintype "passive"))
      (node (ref "SW1") (pin "B") (pinfunction "B_B") (pintype "passive"))
      (node (ref "SW1") (pin "B'") (pinfunction "B'_B'") (pintype "passive"))
    )
    (net (code "40") (name "VCC") (class "Default")
      (node (ref "C11") (pin "2") (pinfunction "2_2") (pintype "passive"))
      (node (ref "C12") (pin "2") (pinfunction "2_2") (pintype "passive"))
      (node (ref "C14") (pin "2") (pinfunction "2_2") (pintype "passive"))
      (node (ref "C16") (pin "2") (pinfunction "2_2") (pintype "passive"))
      (node (ref "C18") (pin "2") (pinfunction "2_2") (pintype "passive"))
      (node (ref "J2") (pin "1") (pinfunction "1_1") (pintype "passive"))
      (node (ref "J2") (pin "2") (pinfunction "2_2") (pintype "passive"))
      (node (ref "J3") (pin "1") (pinfunction "1_1") (pintype "passive"))
      (node (ref "J3") (pin "2") (pinfunction "2_2") (pintype "passive"))
      (node (ref "J4") (pin "1") (pinfunction "1_1") (pintype "passive"))
      (node (ref "J4") (pin "2") (pinfunction "2_2") (pintype "passive"))
      (node (ref "J5") (pin "1") (pinfunction "1_1") (pintype "passive"))
      (node (ref "J5") (pin "2") (pinfunction "2_2") (pintype "passive"))
      (node (ref "U4") (pin "3") (pinfunction "ON/OFF_3") (pintype "passive"))
      (node (ref "U4") (pin "6") (pinfunction "VIN_6") (pintype "power_in"))
    )
    (net (code "41") (name "unconnected-(SW2-PadA)") (class "Default")
      (node (ref "SW2") (pin "A") (pinfunction "A_A") (pintype "passive"))
    )
    (net (code "42") (name "unconnected-(SW2-PadB')") (class "Default")
      (node (ref "SW2") (pin "B'") (pinfunction "B'_B'") (pintype "passive"))
    )
    (net (code "43") (name "unconnected-(U1-IO1-Pad39)") (class "Default")
      (node (ref "U1") (pin "39") (pinfunction "IO1_39") (pintype "bidirectional"))
    )
    (net (code "44") (name "unconnected-(U1-IO2-Pad38)") (class "Default")
      (node (ref "U1") (pin "38") (pinfunction "IO2_38") (pintype "bidirectional"))
    )
    (net (code "45") (name "unconnected-(U1-IO5-Pad5)") (class "Default")
      (node (ref "U1") (pin "5") (pinfunction "IO5_5") (pintype "bidirectional"))
    )
    (net (code "46") (name "unconnected-(U1-IO6-Pad6)") (class "Default")
      (node (ref "U1") (pin "6") (pinfunction "IO6_6") (pintype "bidirectional"))
    )
    (net (code "47") (name "unconnected-(U1-IO7-Pad7)") (class "Default")
      (node (ref "U1") (pin "7") (pinfunction "IO7_7") (pintype "bidirectional"))
    )
    (net (code "48") (name "unconnected-(U1-IO8-Pad12)") (class "Default")
      (node (ref "U1") (pin "12") (pinfunction "IO8_12") (pintype "bidirectional"))
    )
    (net (code "49") (name "unconnected-(U1-IO35-Pad28)") (class "Default")
      (node (ref "U1") (pin "28") (pinfunction "IO35_28") (pintype "bidirectional"))
    )
    (net (code "50") (name "unconnected-(U1-IO39-Pad32)") (class "Default")
      (node (ref "U1") (pin "32") (pinfunction "IO39_32") (pintype "bidirectional"))
    )
    (net (code "51") (name "unconnected-(U1-IO40-Pad33)") (class "Default")
      (node (ref "U1") (pin "33") (pinfunction "IO40_33") (pintype "bidirectional"))
    )
    (net (code "52") (name "unconnected-(U1-IO41-Pad34)") (class "Default")
      (node (ref "U1") (pin "34") (pinfunction "IO41_34") (pintype "bidirectional"))
    )
    (net (code "53") (name "unconnected-(U1-RXD0-Pad36)") (class "Default")
      (node (ref "U1") (pin "36") (pinfunction "RXD0_36") (pintype "bidirectional"))
    )
    (net (code "54") (name "unconnected-(U1-TXD0-Pad37)") (class "Default")
      (node (ref "U1") (pin "37") (pinfunction "TXD0_37") (pintype "bidirectional"))
    )
    (net (code "55") (name "unconnected-(U4-NC-Pad4)") (class "Default")
      (node (ref "U4") (pin "4") (pinfunction "NC_4") (pintype "passive+no_connect"))
    )
  )
)
